# Main.net
KiCad netlist of a schematic drawn in Altium Designer
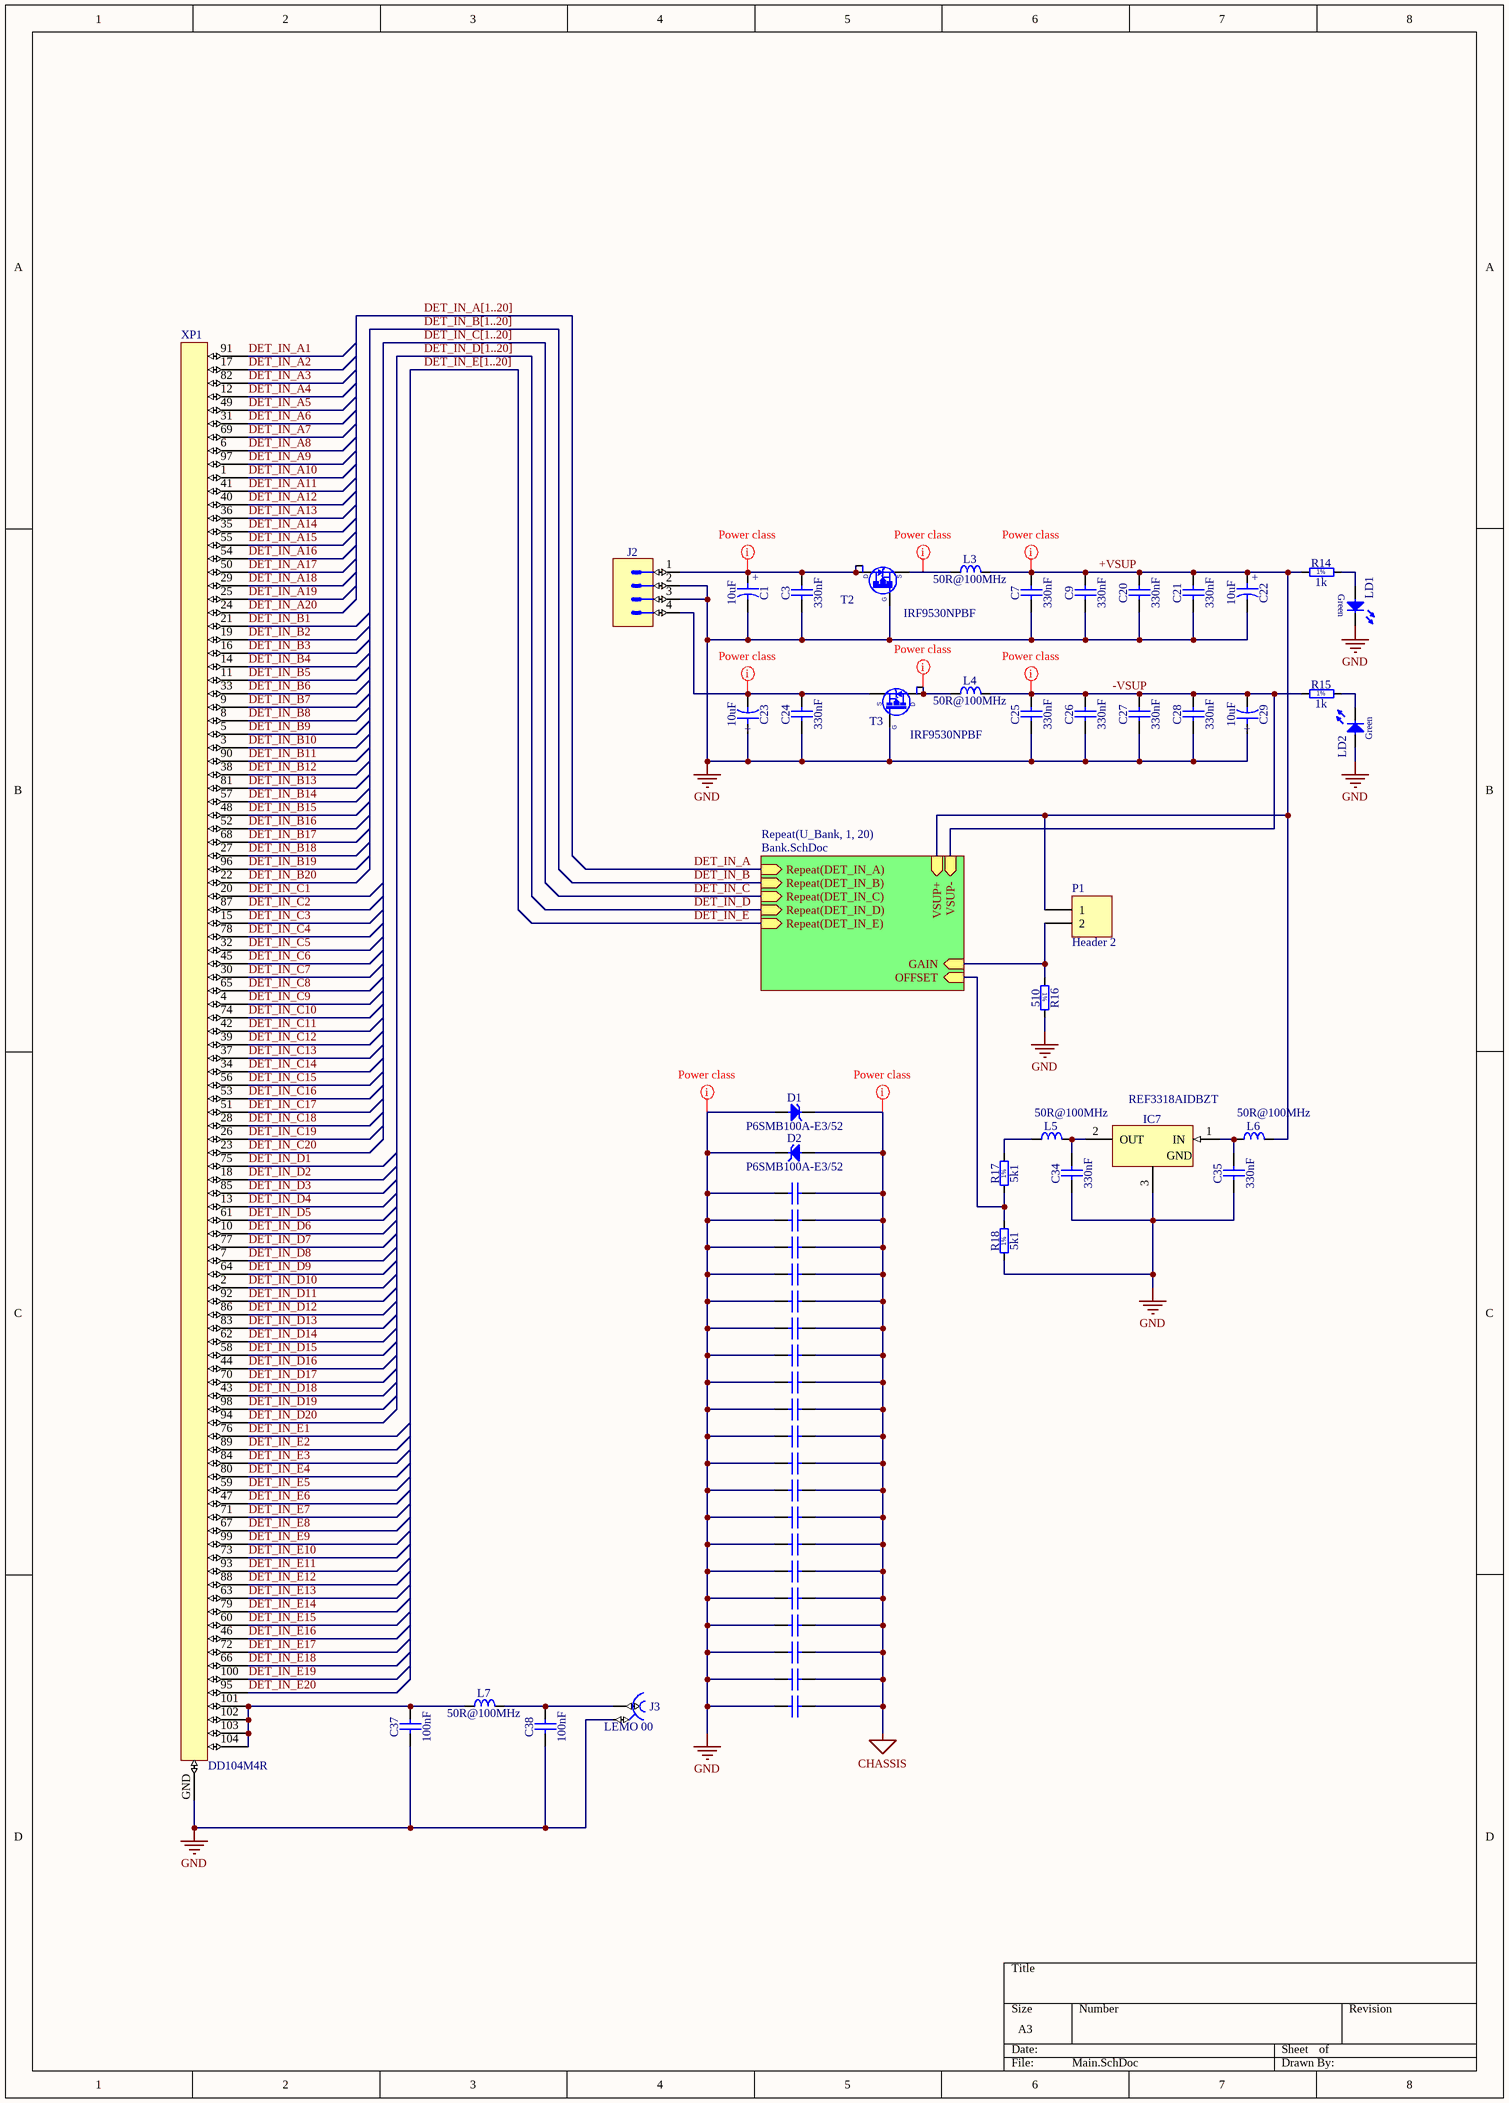
[diagram p0: Main.SchDoc]

(export (version "E")
  (design (tool "Eeschema 10.0.6"))
  (components
    (comp (ref "C1")
      (value "10uF")
      (footprint "CAPAE430X540N")
      (description "Polarised capacitor")
      (fields
        (field (name "PART NUMBER") "CAE430-540_10UF_16V_20%")
        (field (name "VOLTAGE") "16V")
        (field (name "AUTHOR") "CERN DEM JLC")
      )
      (libsource (lib "Capacitors") (part "Capacitor - polarized"))
    )
    (comp (ref "C3")
      (value "330nF")
      (footprint "CAPC2012X145N")
      (description "Non-polarised capacitor")
      (fields
        (field (name "PART NUMBER") "CC0805_330NF_50V_20%_X5R")
        (field (name "VOLTAGE") "50V")
        (field (name "AUTHOR") "CERN DEM MR")
      )
      (libsource (lib "Capacitors") (part "Capacitor - non polarized"))
    )
    (comp (ref "C7")
      (value "330nF")
      (footprint "CAPC2012X145N")
      (description "Non-polarised capacitor")
      (fields
        (field (name "PART NUMBER") "CC0805_330NF_50V_20%_X5R")
        (field (name "VOLTAGE") "50V")
        (field (name "AUTHOR") "CERN DEM MR")
      )
      (libsource (lib "Capacitors") (part "Capacitor - non polarized"))
    )
    (comp (ref "C9")
      (value "330nF")
      (footprint "CAPC2012X145N")
      (description "Non-polarised capacitor")
      (fields
        (field (name "PART NUMBER") "CC0805_330NF_50V_20%_X5R")
        (field (name "VOLTAGE") "50V")
        (field (name "AUTHOR") "CERN DEM MR")
      )
      (libsource (lib "Capacitors") (part "Capacitor - non polarized"))
    )
    (comp (ref "C20")
      (value "330nF")
      (footprint "CAPC2012X145N")
      (description "Non-polarised capacitor")
      (fields
        (field (name "PART NUMBER") "CC0805_330NF_50V_20%_X5R")
        (field (name "VOLTAGE") "50V")
        (field (name "AUTHOR") "CERN DEM MR")
      )
      (libsource (lib "Capacitors") (part "Capacitor - non polarized"))
    )
    (comp (ref "C21")
      (value "330nF")
      (footprint "CAPC2012X145N")
      (description "Non-polarised capacitor")
      (fields
        (field (name "PART NUMBER") "CC0805_330NF_50V_20%_X5R")
        (field (name "VOLTAGE") "50V")
        (field (name "AUTHOR") "CERN DEM MR")
      )
      (libsource (lib "Capacitors") (part "Capacitor - non polarized"))
    )
    (comp (ref "C22")
      (value "10uF")
      (footprint "CAPAE430X540N")
      (description "Polarised capacitor")
      (fields
        (field (name "PART NUMBER") "CAE430-540_10UF_16V_20%")
        (field (name "VOLTAGE") "16V")
        (field (name "AUTHOR") "CERN DEM JLC")
      )
      (libsource (lib "Capacitors") (part "Capacitor - polarized"))
    )
    (comp (ref "C23")
      (value "10uF")
      (footprint "CAPAE430X540N")
      (description "Polarised capacitor")
      (fields
        (field (name "PART NUMBER") "CAE430-540_10UF_16V_20%")
        (field (name "VOLTAGE") "16V")
        (field (name "AUTHOR") "CERN DEM JLC")
      )
      (libsource (lib "") (part "Capacitor - polarized_1"))
    )
    (comp (ref "C24")
      (value "330nF")
      (footprint "CAPC2012X145N")
      (description "Non-polarised capacitor")
      (fields
        (field (name "PART NUMBER") "CC0805_330NF_50V_20%_X5R")
        (field (name "VOLTAGE") "50V")
        (field (name "AUTHOR") "CERN DEM MR")
      )
      (libsource (lib "Capacitors") (part "Capacitor - non polarized"))
    )
    (comp (ref "C25")
      (value "330nF")
      (footprint "CAPC2012X145N")
      (description "Non-polarised capacitor")
      (fields
        (field (name "PART NUMBER") "CC0805_330NF_50V_20%_X5R")
        (field (name "VOLTAGE") "50V")
        (field (name "AUTHOR") "CERN DEM MR")
      )
      (libsource (lib "Capacitors") (part "Capacitor - non polarized"))
    )
    (comp (ref "C26")
      (value "330nF")
      (footprint "CAPC2012X145N")
      (description "Non-polarised capacitor")
      (fields
        (field (name "PART NUMBER") "CC0805_330NF_50V_20%_X5R")
        (field (name "VOLTAGE") "50V")
        (field (name "AUTHOR") "CERN DEM MR")
      )
      (libsource (lib "Capacitors") (part "Capacitor - non polarized"))
    )
    (comp (ref "C27")
      (value "330nF")
      (footprint "CAPC2012X145N")
      (description "Non-polarised capacitor")
      (fields
        (field (name "PART NUMBER") "CC0805_330NF_50V_20%_X5R")
        (field (name "VOLTAGE") "50V")
        (field (name "AUTHOR") "CERN DEM MR")
      )
      (libsource (lib "Capacitors") (part "Capacitor - non polarized"))
    )
    (comp (ref "C28")
      (value "330nF")
      (footprint "CAPC2012X145N")
      (description "Non-polarised capacitor")
      (fields
        (field (name "PART NUMBER") "CC0805_330NF_50V_20%_X5R")
        (field (name "VOLTAGE") "50V")
        (field (name "AUTHOR") "CERN DEM MR")
      )
      (libsource (lib "Capacitors") (part "Capacitor - non polarized"))
    )
    (comp (ref "C29")
      (value "10uF")
      (footprint "CAPAE430X540N")
      (description "Polarised capacitor")
      (fields
        (field (name "PART NUMBER") "CAE430-540_10UF_16V_20%")
        (field (name "VOLTAGE") "16V")
        (field (name "AUTHOR") "CERN DEM JLC")
      )
      (libsource (lib "") (part "Capacitor - polarized_1"))
    )
    (comp (ref "C31")
      (value "100nF")
      (footprint "CAPC3216X140N")
      (description "Non-polarised capacitor")
      (fields
        (field (name "PART NUMBER") "CC1206_100NF_200V_10%_X7R")
        (field (name "VOLTAGE") "200V")
        (field (name "AUTHOR") "CERN DEM JLC")
      )
      (libsource (lib "Capacitors") (part "Capacitor - non polarized"))
    )
    (comp (ref "C32")
      (value "100nF")
      (footprint "CAPC3216X140N")
      (description "Non-polarised capacitor")
      (fields
        (field (name "PART NUMBER") "CC1206_100NF_200V_10%_X7R")
        (field (name "VOLTAGE") "200V")
        (field (name "AUTHOR") "CERN DEM JLC")
      )
      (libsource (lib "Capacitors") (part "Capacitor - non polarized"))
    )
    (comp (ref "C33")
      (value "100nF")
      (footprint "CAPC3216X140N")
      (description "Non-polarised capacitor")
      (fields
        (field (name "PART NUMBER") "CC1206_100NF_200V_10%_X7R")
        (field (name "VOLTAGE") "200V")
        (field (name "AUTHOR") "CERN DEM JLC")
      )
      (libsource (lib "Capacitors") (part "Capacitor - non polarized"))
    )
    (comp (ref "C34")
      (value "330nF")
      (footprint "CAPC2012X145N")
      (description "Non-polarised capacitor")
      (fields
        (field (name "PART NUMBER") "CC0805_330NF_50V_20%_X5R")
        (field (name "VOLTAGE") "50V")
        (field (name "AUTHOR") "CERN DEM MR")
      )
      (libsource (lib "Capacitors") (part "Capacitor - non polarized"))
    )
    (comp (ref "C35")
      (value "330nF")
      (footprint "CAPC2012X145N")
      (description "Non-polarised capacitor")
      (fields
        (field (name "PART NUMBER") "CC0805_330NF_50V_20%_X5R")
        (field (name "VOLTAGE") "50V")
        (field (name "AUTHOR") "CERN DEM MR")
      )
      (libsource (lib "Capacitors") (part "Capacitor - non polarized"))
    )
    (comp (ref "C36")
      (value "100nF")
      (footprint "CAPC3216X140N")
      (description "Non-polarised capacitor")
      (fields
        (field (name "PART NUMBER") "CC1206_100NF_200V_10%_X7R")
        (field (name "VOLTAGE") "200V")
        (field (name "AUTHOR") "CERN DEM JLC")
      )
      (libsource (lib "Capacitors") (part "Capacitor - non polarized"))
    )
    (comp (ref "C37")
      (value "100nF")
      (footprint "CAPC3216X140N")
      (description "Non-polarised capacitor")
      (fields
        (field (name "PART NUMBER") "CC1206_100NF_200V_10%_X7R")
        (field (name "VOLTAGE") "200V")
        (field (name "AUTHOR") "CERN DEM JLC")
      )
      (libsource (lib "Capacitors") (part "Capacitor - non polarized"))
    )
    (comp (ref "C38")
      (value "100nF")
      (footprint "CAPC3216X140N")
      (description "Non-polarised capacitor")
      (fields
        (field (name "PART NUMBER") "CC1206_100NF_200V_10%_X7R")
        (field (name "VOLTAGE") "200V")
        (field (name "AUTHOR") "CERN DEM JLC")
      )
      (libsource (lib "Capacitors") (part "Capacitor - non polarized"))
    )
    (comp (ref "C39")
      (value "100nF")
      (footprint "CAPC3216X140N")
      (description "Non-polarised capacitor")
      (fields
        (field (name "PART NUMBER") "CC1206_100NF_200V_10%_X7R")
        (field (name "VOLTAGE") "200V")
        (field (name "AUTHOR") "CERN DEM JLC")
      )
      (libsource (lib "Capacitors") (part "Capacitor - non polarized"))
    )
    (comp (ref "C40")
      (value "100nF")
      (footprint "CAPC3216X140N")
      (description "Non-polarised capacitor")
      (fields
        (field (name "PART NUMBER") "CC1206_100NF_200V_10%_X7R")
        (field (name "VOLTAGE") "200V")
        (field (name "AUTHOR") "CERN DEM JLC")
      )
      (libsource (lib "Capacitors") (part "Capacitor - non polarized"))
    )
    (comp (ref "C41")
      (value "100nF")
      (footprint "CAPC3216X140N")
      (description "Non-polarised capacitor")
      (fields
        (field (name "PART NUMBER") "CC1206_100NF_200V_10%_X7R")
        (field (name "VOLTAGE") "200V")
        (field (name "AUTHOR") "CERN DEM JLC")
      )
      (libsource (lib "Capacitors") (part "Capacitor - non polarized"))
    )
    (comp (ref "C42")
      (value "100nF")
      (footprint "CAPC3216X140N")
      (description "Non-polarised capacitor")
      (fields
        (field (name "PART NUMBER") "CC1206_100NF_200V_10%_X7R")
        (field (name "VOLTAGE") "200V")
        (field (name "AUTHOR") "CERN DEM JLC")
      )
      (libsource (lib "Capacitors") (part "Capacitor - non polarized"))
    )
    (comp (ref "C43")
      (value "100nF")
      (footprint "CAPC3216X140N")
      (description "Non-polarised capacitor")
      (fields
        (field (name "PART NUMBER") "CC1206_100NF_200V_10%_X7R")
        (field (name "VOLTAGE") "200V")
        (field (name "AUTHOR") "CERN DEM JLC")
      )
      (libsource (lib "Capacitors") (part "Capacitor - non polarized"))
    )
    (comp (ref "C44")
      (value "100nF")
      (footprint "CAPC3216X140N")
      (description "Non-polarised capacitor")
      (fields
        (field (name "PART NUMBER") "CC1206_100NF_200V_10%_X7R")
        (field (name "VOLTAGE") "200V")
        (field (name "AUTHOR") "CERN DEM JLC")
      )
      (libsource (lib "Capacitors") (part "Capacitor - non polarized"))
    )
    (comp (ref "C45")
      (value "100nF")
      (footprint "CAPC3216X140N")
      (description "Non-polarised capacitor")
      (fields
        (field (name "PART NUMBER") "CC1206_100NF_200V_10%_X7R")
        (field (name "VOLTAGE") "200V")
        (field (name "AUTHOR") "CERN DEM JLC")
      )
      (libsource (lib "Capacitors") (part "Capacitor - non polarized"))
    )
    (comp (ref "C46")
      (value "100nF")
      (footprint "CAPC3216X140N")
      (description "Non-polarised capacitor")
      (fields
        (field (name "PART NUMBER") "CC1206_100NF_200V_10%_X7R")
        (field (name "VOLTAGE") "200V")
        (field (name "AUTHOR") "CERN DEM JLC")
      )
      (libsource (lib "Capacitors") (part "Capacitor - non polarized"))
    )
    (comp (ref "C47")
      (value "100nF")
      (footprint "CAPC3216X140N")
      (description "Non-polarised capacitor")
      (fields
        (field (name "PART NUMBER") "CC1206_100NF_200V_10%_X7R")
        (field (name "VOLTAGE") "200V")
        (field (name "AUTHOR") "CERN DEM JLC")
      )
      (libsource (lib "Capacitors") (part "Capacitor - non polarized"))
    )
    (comp (ref "C48")
      (value "100nF")
      (footprint "CAPC3216X140N")
      (description "Non-polarised capacitor")
      (fields
        (field (name "PART NUMBER") "CC1206_100NF_200V_10%_X7R")
        (field (name "VOLTAGE") "200V")
        (field (name "AUTHOR") "CERN DEM JLC")
      )
      (libsource (lib "Capacitors") (part "Capacitor - non polarized"))
    )
    (comp (ref "C49")
      (value "100nF")
      (footprint "CAPC3216X140N")
      (description "Non-polarised capacitor")
      (fields
        (field (name "PART NUMBER") "CC1206_100NF_200V_10%_X7R")
        (field (name "VOLTAGE") "200V")
        (field (name "AUTHOR") "CERN DEM JLC")
      )
      (libsource (lib "Capacitors") (part "Capacitor - non polarized"))
    )
    (comp (ref "C50")
      (value "100nF")
      (footprint "CAPC3216X140N")
      (description "Non-polarised capacitor")
      (fields
        (field (name "PART NUMBER") "CC1206_100NF_200V_10%_X7R")
        (field (name "VOLTAGE") "200V")
        (field (name "AUTHOR") "CERN DEM JLC")
      )
      (libsource (lib "Capacitors") (part "Capacitor - non polarized"))
    )
    (comp (ref "C51")
      (value "100nF")
      (footprint "CAPC3216X140N")
      (description "Non-polarised capacitor")
      (fields
        (field (name "PART NUMBER") "CC1206_100NF_200V_10%_X7R")
        (field (name "VOLTAGE") "200V")
        (field (name "AUTHOR") "CERN DEM JLC")
      )
      (libsource (lib "Capacitors") (part "Capacitor - non polarized"))
    )
    (comp (ref "C52")
      (value "100nF")
      (footprint "CAPC3216X140N")
      (description "Non-polarised capacitor")
      (fields
        (field (name "PART NUMBER") "CC1206_100NF_200V_10%_X7R")
        (field (name "VOLTAGE") "200V")
        (field (name "AUTHOR") "CERN DEM JLC")
      )
      (libsource (lib "Capacitors") (part "Capacitor - non polarized"))
    )
    (comp (ref "C53")
      (value "100nF")
      (footprint "CAPC3216X140N")
      (description "Non-polarised capacitor")
      (fields
        (field (name "PART NUMBER") "CC1206_100NF_200V_10%_X7R")
        (field (name "VOLTAGE") "200V")
        (field (name "AUTHOR") "CERN DEM JLC")
      )
      (libsource (lib "Capacitors") (part "Capacitor - non polarized"))
    )
    (comp (ref "C54")
      (value "100nF")
      (footprint "CAPC3216X140N")
      (description "Non-polarised capacitor")
      (fields
        (field (name "PART NUMBER") "CC1206_100NF_200V_10%_X7R")
        (field (name "VOLTAGE") "200V")
        (field (name "AUTHOR") "CERN DEM JLC")
      )
      (libsource (lib "Capacitors") (part "Capacitor - non polarized"))
    )
    (comp (ref "D1")
      (value "P6SMB100A-E3/52")
      (footprint "DIOM5436X244N")
      (description "Transient Voltage Suppressor Diode (Uni-Directional)")
      (fields
        (field (name "VOLTAGE") "100V")
        (field (name "POWER") "600W")
        (field (name "AUTHOR") "CERN DEM JLC")
      )
      (libsource (lib "ICs And Semiconductors") (part "Diode TVS Uni-Directional"))
    )
    (comp (ref "D2")
      (value "P6SMB100A-E3/52")
      (footprint "DIOM5436X244N")
      (description "Transient Voltage Suppressor Diode (Uni-Directional)")
      (fields
        (field (name "VOLTAGE") "100V")
        (field (name "POWER") "600W")
        (field (name "AUTHOR") "CERN DEM JLC")
      )
      (libsource (lib "ICs And Semiconductors") (part "Diode TVS Uni-Directional"))
    )
    (comp (ref "IC7")
      (value "REF3318AIDBZT")
      (footprint "SOT95P237X112-3N")
      (description "3-Terminal Regulator 1=IN 2=OUT 3=GND")
      (fields (field (name "MANUFACTURER") "TEXAS INSTRUMENTS") (field (name "AUTHOR") "CERN DEM JLC"))
      (libsource (lib "ICs And Semiconductors") (part "REG3 1IN-2OUT-3GND"))
    )
    (comp (ref "J2")
      (value "Header 4")
      (footprint "WURTH_691 313 410 004")
      (description "Connector 4 Male")
      (fields
        (field (name "PART NUMBER") "WURTH_691 313 410 004")
        (field (name "MANUFACTURER") "WURTH ELEKTRONIK")
        (field (name "AUTHOR") "CERN DEM MR")
      )
      (libsource (lib "Connectors") (part "Connector 4 Male"))
    )
    (comp (ref "J3")
      (value "LEMO 00")
      (footprint "LEMO_EPK.00.250.NTN")
      (fields
        (field (name "PART NUMBER") "LEMO_EPK.00.250.NTN")
        (field (name "MANUFACTURER") "LEMO")
        (field (name "MANUFACTURER PART NUMBER") "EPK.00.250.NTN")
        (field (name "AUTHOR") "CERN DEM JLC")
      )
      (libsource (lib "Connectors") (part "Coax_1Female_1Shield"))
    )
    (comp (ref "L3")
      (value "50R@100MHz")
      (footprint "IND_MURATA_BLM31PG")
      (description "Inductor")
      (fields
        (field (name "PART NUMBER") "IND1206_MURATA_BLM31PG500SN1")
        (field (name "POWER") "3.5A")
        (field (name "AUTHOR") "CERN DEM JLC")
      )
      (libsource (lib "Inductors & Transformers") (part "Inductor"))
    )
    (comp (ref "L4")
      (value "50R@100MHz")
      (footprint "IND_MURATA_BLM31PG")
      (description "Inductor")
      (fields
        (field (name "PART NUMBER") "IND1206_MURATA_BLM31PG500SN1")
        (field (name "POWER") "3.5A")
        (field (name "AUTHOR") "CERN DEM JLC")
      )
      (libsource (lib "Inductors & Transformers") (part "Inductor"))
    )
    (comp (ref "L5")
      (value "50R@100MHz")
      (footprint "IND_MURATA_BLM31PG")
      (description "Inductor")
      (fields
        (field (name "PART NUMBER") "IND1206_MURATA_BLM31PG500SN1")
        (field (name "POWER") "3.5A")
        (field (name "AUTHOR") "CERN DEM JLC")
      )
      (libsource (lib "Inductors & Transformers") (part "Inductor"))
    )
    (comp (ref "L6")
      (value "50R@100MHz")
      (footprint "IND_MURATA_BLM31PG")
      (description "Inductor")
      (fields
        (field (name "PART NUMBER") "IND1206_MURATA_BLM31PG500SN1")
        (field (name "POWER") "3.5A")
        (field (name "AUTHOR") "CERN DEM JLC")
      )
      (libsource (lib "Inductors & Transformers") (part "Inductor"))
    )
    (comp (ref "L7")
      (value "50R@100MHz")
      (footprint "IND_MURATA_BLM31PG")
      (description "Inductor")
      (fields
        (field (name "PART NUMBER") "IND1206_MURATA_BLM31PG500SN1")
        (field (name "POWER") "3.5A")
        (field (name "AUTHOR") "CERN DEM JLC")
      )
      (libsource (lib "Inductors & Transformers") (part "Inductor"))
    )
    (comp (ref "LD1")
      (value "Green")
      (footprint "LED_OSRAM_LGR971")
      (description "LED Green 1C 2A")
      (fields
        (field (name "PART NUMBER") "LED_OSRAM_LGR971")
        (field (name "MANUFACTURER") "OSRAM")
        (field (name "AUTHOR") "CERN DEM JLC")
      )
      (libsource (lib "ICs And Semiconductors") (part "LED Green 1C 2A"))
    )
    (comp (ref "LD2")
      (value "Green")
      (footprint "LED_OSRAM_LGR971")
      (description "LED Green 1C 2A")
      (fields
        (field (name "PART NUMBER") "LED_OSRAM_LGR971")
        (field (name "MANUFACTURER") "OSRAM")
        (field (name "AUTHOR") "CERN DEM JLC")
      )
      (libsource (lib "ICs And Semiconductors") (part "LED Green 1C 2A"))
    )
    (comp (ref "P1")
      (value "Header 2")
      (footprint "HDR1X2")
      (description "Header, 2-Pin")
      (fields (field (name "PUBLISHER") "Altium Limited"))
      (libsource (lib "Miscellaneous Connectors") (part "Header 2"))
    )
    (comp (ref "R14")
      (value "1k")
      (footprint "RESC2012X60N")
      (description "Resistor - 1%")
      (fields
        (field (name "PART NUMBER") "R0805_1K_1%_0.125W_100PPM")
        (field (name "POWER") "0.125W")
        (field (name "AUTHOR") "CERN DEM JLC")
      )
      (libsource (lib "Resistors") (part "Resistor - 1%"))
    )
    (comp (ref "R15")
      (value "1k")
      (footprint "RESC2012X60N")
      (description "Resistor - 1%")
      (fields
        (field (name "PART NUMBER") "R0805_1K_1%_0.125W_100PPM")
        (field (name "POWER") "0.125W")
        (field (name "AUTHOR") "CERN DEM JLC")
      )
      (libsource (lib "Resistors") (part "Resistor - 1%"))
    )
    (comp (ref "R16")
      (value "510")
      (footprint "RESC2012X60N")
      (description "Resistor - 1%")
      (fields
        (field (name "PART NUMBER") "R0805_510R_1%_0.125W_100PPM")
        (field (name "POWER") "0.125W")
        (field (name "AUTHOR") "CERN DEM JLC")
      )
      (libsource (lib "Resistors") (part "Resistor - 1%"))
    )
    (comp (ref "R17")
      (value "5k1")
      (footprint "RESC2012X60N")
      (description "Resistor - 1%")
      (fields
        (field (name "PART NUMBER") "R0805_5K1_1%_0.125W_100PPM")
        (field (name "POWER") "0.125W")
        (field (name "AUTHOR") "CERN DEM JLC")
      )
      (libsource (lib "Resistors") (part "Resistor - 1%"))
    )
    (comp (ref "R18")
      (value "5k1")
      (footprint "RESC2012X60N")
      (description "Resistor - 1%")
      (fields
        (field (name "PART NUMBER") "R0805_5K1_1%_0.125W_100PPM")
        (field (name "POWER") "0.125W")
        (field (name "AUTHOR") "CERN DEM JLC")
      )
      (libsource (lib "Resistors") (part "Resistor - 1%"))
    )
    (comp (ref "T2")
      (value "IRF9530NPBF")
      (footprint "TO-220-H")
      (description "P-CHANNEL MOSFET WITH ZENER DIODE")
      (fields
        (field (name "PART NUMBER") "IRF9530NPBF_h")
        (field (name "MANUFACTURER") "INTERNATIONAL RECTIFIER")
        (field (name "AUTHOR") "CERN DEM MR")
      )
      (libsource (lib "") (part "P-MOSFET-DZ 1G 2D 3S 4D_1"))
    )
    (comp (ref "T3")
      (value "IRF9530NPBF")
      (footprint "TO-220-H")
      (description "P-CHANNEL MOSFET WITH ZENER DIODE")
      (fields
        (field (name "PART NUMBER") "IRF9530NPBF_h")
        (field (name "MANUFACTURER") "INTERNATIONAL RECTIFIER")
        (field (name "AUTHOR") "CERN DEM MR")
      )
      (libsource (lib "ICs And Semiconductors") (part "P-MOSFET-DZ 1G 2D 3S 4D"))
    )
    (comp (ref "XP1") (value "DD104M4R") (footprint "DB104") (libsource (lib "Schlib") (part "DD104M4R")))
  )
  (nets
    (net (code "1") (name "/+VSUP") (class "Default")
      (node (ref "C20") (pin "2") (pinfunction "2_2") (pintype "passive"))
      (node (ref "C21") (pin "2") (pinfunction "2_2") (pintype "passive"))
      (node (ref "C22") (pin "1") (pinfunction "1_1") (pintype "passive"))
      (node (ref "C7") (pin "2") (pinfunction "2_2") (pintype "passive"))
      (node (ref "C9") (pin "2") (pinfunction "2_2") (pintype "passive"))
      (node (ref "L3") (pin "2") (pinfunction "2_2") (pintype "passive"))
      (node (ref "L6") (pin "2") (pinfunction "2_2") (pintype "passive"))
      (node (ref "P1") (pin "1") (pinfunction "1_1") (pintype "passive"))
      (node (ref "R14") (pin "1") (pinfunction "1_1") (pintype "passive"))
    )
    (net (code "2") (name "/-VSUP") (class "Default")
      (node (ref "C25") (pin "2") (pinfunction "2_2") (pintype "passive"))
      (node (ref "C26") (pin "2") (pinfunction "2_2") (pintype "passive"))
      (node (ref "C27") (pin "2") (pinfunction "2_2") (pintype "passive"))
      (node (ref "C28") (pin "2") (pinfunction "2_2") (pintype "passive"))
      (node (ref "C29") (pin "2") (pinfunction "2_2") (pintype "passive"))
      (node (ref "L4") (pin "2") (pinfunction "2_2") (pintype "passive"))
      (node (ref "R15") (pin "1") (pinfunction "1_1") (pintype "passive"))
    )
    (net (code "4") (name "/DET_IN_A1") (class "Default")
      (node (ref "XP1") (pin "91") (pintype "bidirectional"))
    )
    (net (code "5") (name "/DET_IN_A2") (class "Default")
      (node (ref "XP1") (pin "17") (pintype "bidirectional"))
    )
    (net (code "6") (name "/DET_IN_A3") (class "Default")
      (node (ref "XP1") (pin "82") (pintype "bidirectional"))
    )
    (net (code "7") (name "/DET_IN_A4") (class "Default")
      (node (ref "XP1") (pin "12") (pintype "bidirectional"))
    )
    (net (code "8") (name "/DET_IN_A5") (class "Default")
      (node (ref "XP1") (pin "49") (pintype "bidirectional"))
    )
    (net (code "9") (name "/DET_IN_A6") (class "Default")
      (node (ref "XP1") (pin "31") (pintype "bidirectional"))
    )
    (net (code "10") (name "/DET_IN_A7") (class "Default")
      (node (ref "XP1") (pin "69") (pintype "bidirectional"))
    )
    (net (code "11") (name "/DET_IN_A8") (class "Default")
      (node (ref "XP1") (pin "6") (pintype "bidirectional"))
    )
    (net (code "12") (name "/DET_IN_A9") (class "Default")
      (node (ref "XP1") (pin "97") (pintype "bidirectional"))
    )
    (net (code "13") (name "/DET_IN_A10") (class "Default")
      (node (ref "XP1") (pin "1") (pintype "bidirectional"))
    )
    (net (code "14") (name "/DET_IN_A11") (class "Default")
      (node (ref "XP1") (pin "41") (pintype "bidirectional"))
    )
    (net (code "15") (name "/DET_IN_A12") (class "Default")
      (node (ref "XP1") (pin "40") (pintype "bidirectional"))
    )
    (net (code "16") (name "/DET_IN_A13") (class "Default")
      (node (ref "XP1") (pin "36") (pintype "bidirectional"))
    )
    (net (code "17") (name "/DET_IN_A14") (class "Default")
      (node (ref "XP1") (pin "35") (pintype "bidirectional"))
    )
    (net (code "18") (name "/DET_IN_A15") (class "Default")
      (node (ref "XP1") (pin "55") (pintype "bidirectional"))
    )
    (net (code "19") (name "/DET_IN_A16") (class "Default")
      (node (ref "XP1") (pin "54") (pintype "bidirectional"))
    )
    (net (code "20") (name "/DET_IN_A17") (class "Default")
      (node (ref "XP1") (pin "50") (pintype "bidirectional"))
    )
    (net (code "21") (name "/DET_IN_A18") (class "Default")
      (node (ref "XP1") (pin "29") (pintype "bidirectional"))
    )
    (net (code "22") (name "/DET_IN_A19") (class "Default")
      (node (ref "XP1") (pin "25") (pintype "bidirectional"))
    )
    (net (code "23") (name "/DET_IN_A20") (class "Default")
      (node (ref "XP1") (pin "24") (pintype "bidirectional"))
    )
    (net (code "26") (name "/DET_IN_B1") (class "Default")
      (node (ref "XP1") (pin "21") (pintype "bidirectional"))
    )
    (net (code "27") (name "/DET_IN_B2") (class "Default")
      (node (ref "XP1") (pin "19") (pintype "bidirectional"))
    )
    (net (code "28") (name "/DET_IN_B3") (class "Default")
      (node (ref "XP1") (pin "16") (pintype "bidirectional"))
    )
    (net (code "29") (name "/DET_IN_B4") (class "Default")
      (node (ref "XP1") (pin "14") (pintype "bidirectional"))
    )
    (net (code "30") (name "/DET_IN_B5") (class "Default")
      (node (ref "XP1") (pin "11") (pintype "bidirectional"))
    )
    (net (code "31") (name "/DET_IN_B6") (class "Default")
      (node (ref "XP1") (pin "33") (pintype "bidirectional"))
    )
    (net (code "32") (name "/DET_IN_B7") (class "Default")
      (node (ref "XP1") (pin "9") (pintype "bidirectional"))
    )
    (net (code "33") (name "/DET_IN_B8") (class "Default")
      (node (ref "XP1") (pin "8") (pintype "bidirectional"))
    )
    (net (code "34") (name "/DET_IN_B9") (class "Default")
      (node (ref "XP1") (pin "5") (pintype "bidirectional"))
    )
    (net (code "35") (name "/DET_IN_B10") (class "Default")
      (node (ref "XP1") (pin "3") (pintype "bidirectional"))
    )
    (net (code "36") (name "/DET_IN_B11") (class "Default")
      (node (ref "XP1") (pin "90") (pintype "bidirectional"))
    )
    (net (code "37") (name "/DET_IN_B12") (class "Default")
      (node (ref "XP1") (pin "38") (pintype "bidirectional"))
    )
    (net (code "38") (name "/DET_IN_B13") (class "Default")
      (node (ref "XP1") (pin "81") (pintype "bidirectional"))
    )
    (net (code "39") (name "/DET_IN_B14") (class "Default")
      (node (ref "XP1") (pin "57") (pintype "bidirectional"))
    )
    (net (code "40") (name "/DET_IN_B15") (class "Default")
      (node (ref "XP1") (pin "48") (pintype "bidirectional"))
    )
    (net (code "41") (name "/DET_IN_B16") (class "Default")
      (node (ref "XP1") (pin "52") (pintype "bidirectional"))
    )
    (net (code "42") (name "/DET_IN_B17") (class "Default")
      (node (ref "XP1") (pin "68") (pintype "bidirectional"))
    )
    (net (code "43") (name "/DET_IN_B18") (class "Default")
      (node (ref "XP1") (pin "27") (pintype "bidirectional"))
    )
    (net (code "44") (name "/DET_IN_B19") (class "Default")
      (node (ref "XP1") (pin "96") (pintype "bidirectional"))
    )
    (net (code "45") (name "/DET_IN_B20") (class "Default")
      (node (ref "XP1") (pin "22") (pintype "bidirectional"))
    )
    (net (code "48") (name "/DET_IN_C1") (class "Default")
      (node (ref "XP1") (pin "20") (pintype "bidirectional"))
    )
    (net (code "49") (name "/DET_IN_C2") (class "Default")
      (node (ref "XP1") (pin "87") (pintype "bidirectional"))
    )
    (net (code "50") (name "/DET_IN_C3") (class "Default")
      (node (ref "XP1") (pin "15") (pintype "bidirectional"))
    )
    (net (code "51") (name "/DET_IN_C4") (class "Default")
      (node (ref "XP1") (pin "78") (pintype "bidirectional"))
    )
    (net (code "52") (name "/DET_IN_C5") (class "Default")
      (node (ref "XP1") (pin "32") (pintype "bidirectional"))
    )
    (net (code "53") (name "/DET_IN_C6") (class "Default")
      (node (ref "XP1") (pin "45") (pintype "bidirectional"))
    )
    (net (code "54") (name "/DET_IN_C7") (class "Default")
      (node (ref "XP1") (pin "30") (pintype "bidirectional"))
    )
    (net (code "55") (name "/DET_IN_C8") (class "Default")
      (node (ref "XP1") (pin "65") (pintype "bidirectional"))
    )
    (net (code "56") (name "/DET_IN_C9") (class "Default")
      (node (ref "XP1") (pin "4") (pintype "bidirectional"))
    )
    (net (code "57") (name "/DET_IN_C10") (class "Default")
      (node (ref "XP1") (pin "74") (pintype "bidirectional"))
    )
    (net (code "58") (name "/DET_IN_C11") (class "Default")
      (node (ref "XP1") (pin "42") (pintype "bidirectional"))
    )
    (net (code "59") (name "/DET_IN_C12") (class "Default")
      (node (ref "XP1") (pin "39") (pintype "bidirectional"))
    )
    (net (code "60") (name "/DET_IN_C13") (class "Default")
      (node (ref "XP1") (pin "37") (pintype "bidirectional"))
    )
    (net (code "61") (name "/DET_IN_C14") (class "Default")
      (node (ref "XP1") (pin "34") (pintype "bidirectional"))
    )
    (net (code "62") (name "/DET_IN_C15") (class "Default")
      (node (ref "XP1") (pin "56") (pintype "bidirectional"))
    )
    (net (code "63") (name "/DET_IN_C16") (class "Default")
      (node (ref "XP1") (pin "53") (pintype "bidirectional"))
    )
    (net (code "64") (name "/DET_IN_C17") (class "Default")
      (node (ref "XP1") (pin "51") (pintype "bidirectional"))
    )
    (net (code "65") (name "/DET_IN_C18") (class "Default")
      (node (ref "XP1") (pin "28") (pintype "bidirectional"))
    )
    (net (code "66") (name "/DET_IN_C19") (class "Default")
      (node (ref "XP1") (pin "26") (pintype "bidirectional"))
    )
    (net (code "67") (name "/DET_IN_C20") (class "Default")
      (node (ref "XP1") (pin "23") (pintype "bidirectional"))
    )
    (net (code "70") (name "/DET_IN_D1") (class "Default")
      (node (ref "XP1") (pin "75") (pintype "bidirectional"))
    )
    (net (code "71") (name "/DET_IN_D2") (class "Default")
      (node (ref "XP1") (pin "18") (pintype "bidirectional"))
    )
    (net (code "72") (name "/DET_IN_D3") (class "Default")
      (node (ref "XP1") (pin "85") (pintype "bidirectional"))
    )
    (net (code "73") (name "/DET_IN_D4") (class "Default")
      (node (ref "XP1") (pin "13") (pintype "bidirectional"))
    )
    (net (code "74") (name "/DET_IN_D5") (class "Default")
      (node (ref "XP1") (pin "61") (pintype "bidirectional"))
    )
    (net (code "75") (name "/DET_IN_D6") (class "Default")
      (node (ref "XP1") (pin "10") (pintype "bidirectional"))
    )
    (net (code "76") (name "/DET_IN_D7") (class "Default")
      (node (ref "XP1") (pin "77") (pintype "bidirectional"))
    )
    (net (code "77") (name "/DET_IN_D8") (class "Default")
      (node (ref "XP1") (pin "7") (pintype "bidirectional"))
    )
    (net (code "78") (name "/DET_IN_D9") (class "Default")
      (node (ref "XP1") (pin "64") (pintype "bidirectional"))
    )
    (net (code "79") (name "/DET_IN_D10") (class "Default")
      (node (ref "XP1") (pin "2") (pintype "bidirectional"))
    )
    (net (code "80") (name "/DET_IN_D11") (class "Default")
      (node (ref "XP1") (pin "92") (pintype "bidirectional"))
    )
    (net (code "81") (name "/DET_IN_D12") (class "Default")
      (node (ref "XP1") (pin "86") (pintype "bidirectional"))
    )
    (net (code "82") (name "/DET_IN_D13") (class "Default")
      (node (ref "XP1") (pin "83") (pintype "bidirectional"))
    )
    (net (code "83") (name "/DET_IN_D14") (class "Default")
      (node (ref "XP1") (pin "62") (pintype "bidirectional"))
    )
    (net (code "84") (name "/DET_IN_D15") (class "Default")
      (node (ref "XP1") (pin "58") (pintype "bidirectional"))
    )
    (net (code "85") (name "/DET_IN_D16") (class "Default")
      (node (ref "XP1") (pin "44") (pintype "bidirectional"))
    )
    (net (code "86") (name "/DET_IN_D17") (class "Default")
      (node (ref "XP1") (pin "70") (pintype "bidirectional"))
    )
    (net (code "87") (name "/DET_IN_D18") (class "Default")
      (node (ref "XP1") (pin "43") (pintype "bidirectional"))
    )
    (net (code "88") (name "/DET_IN_D19") (class "Default")
      (node (ref "XP1") (pin "98") (pintype "bidirectional"))
    )
    (net (code "89") (name "/DET_IN_D20") (class "Default")
      (node (ref "XP1") (pin "94") (pintype "bidirectional"))
    )
    (net (code "92") (name "/DET_IN_E1") (class "Default")
      (node (ref "XP1") (pin "76") (pintype "bidirectional"))
    )
    (net (code "93") (name "/DET_IN_E2") (class "Default")
      (node (ref "XP1") (pin "89") (pintype "bidirectional"))
    )
    (net (code "94") (name "/DET_IN_E3") (class "Default")
      (node (ref "XP1") (pin "84") (pintype "bidirectional"))
    )
    (net (code "95") (name "/DET_IN_E4") (class "Default")
      (node (ref "XP1") (pin "80") (pintype "bidirectional"))
    )
    (net (code "96") (name "/DET_IN_E5") (class "Default")
      (node (ref "XP1") (pin "59") (pintype "bidirectional"))
    )
    (net (code "97") (name "/DET_IN_E6") (class "Default")
      (node (ref "XP1") (pin "47") (pintype "bidirectional"))
    )
    (net (code "98") (name "/DET_IN_E7") (class "Default")
      (node (ref "XP1") (pin "71") (pintype "bidirectional"))
    )
    (net (code "99") (name "/DET_IN_E8") (class "Default")
      (node (ref "XP1") (pin "67") (pintype "bidirectional"))
    )
    (net (code "100") (name "/DET_IN_E9") (class "Default")
      (node (ref "XP1") (pin "99") (pintype "bidirectional"))
    )
    (net (code "101") (name "/DET_IN_E10") (class "Default")
      (node (ref "XP1") (pin "73") (pintype "bidirectional"))
    )
    (net (code "102") (name "/DET_IN_E11") (class "Default")
      (node (ref "XP1") (pin "93") (pintype "bidirectional"))
    )
    (net (code "103") (name "/DET_IN_E12") (class "Default")
      (node (ref "XP1") (pin "88") (pintype "bidirectional"))
    )
    (net (code "104") (name "/DET_IN_E13") (class "Default")
      (node (ref "XP1") (pin "63") (pintype "bidirectional"))
    )
    (net (code "105") (name "/DET_IN_E14") (class "Default")
      (node (ref "XP1") (pin "79") (pintype "bidirectional"))
    )
    (net (code "106") (name "/DET_IN_E15") (class "Default")
      (node (ref "XP1") (pin "60") (pintype "bidirectional"))
    )
    (net (code "107") (name "/DET_IN_E16") (class "Default")
      (node (ref "XP1") (pin "46") (pintype "bidirectional"))
    )
    (net (code "108") (name "/DET_IN_E17") (class "Default")
      (node (ref "XP1") (pin "72") (pintype "bidirectional"))
    )
    (net (code "109") (name "/DET_IN_E18") (class "Default")
      (node (ref "XP1") (pin "66") (pintype "bidirectional"))
    )
    (net (code "110") (name "/DET_IN_E19") (class "Default")
      (node (ref "XP1") (pin "100") (pintype "bidirectional"))
    )
    (net (code "111") (name "/DET_IN_E20") (class "Default")
      (node (ref "XP1") (pin "95") (pintype "bidirectional"))
    )
    (net (code "113") (name "/GAIN") (class "Default")
      (node (ref "P1") (pin "2") (pinfunction "2_2") (pintype "passive"))
      (node (ref "R16") (pin "1") (pinfunction "1_1") (pintype "passive"))
    )
    (net (code "114") (name "/OFFSET") (class "Default")
      (node (ref "R17") (pin "1") (pinfunction "1_1") (pintype "passive"))
      (node (ref "R18") (pin "2") (pinfunction "2_2") (pintype "passive"))
    )
    (net (code "115") (name "CHASSIS") (class "Default")
      (node (ref "C31") (pin "2") (pinfunction "2_2") (pintype "passive"))
      (node (ref "C32") (pin "2") (pinfunction "2_2") (pintype "passive"))
      (node (ref "C33") (pin "2") (pinfunction "2_2") (pintype "passive"))
      (node (ref "C36") (pin "2") (pinfunction "2_2") (pintype "passive"))
      (node (ref "C39") (pin "2") (pinfunction "2_2") (pintype "passive"))
      (node (ref "C40") (pin "2") (pinfunction "2_2") (pintype "passive"))
      (node (ref "C41") (pin "2") (pinfunction "2_2") (pintype "passive"))
      (node (ref "C42") (pin "2") (pinfunction "2_2") (pintype "passive"))
      (node (ref "C43") (pin "2") (pinfunction "2_2") (pintype "passive"))
      (node (ref "C44") (pin "2") (pinfunction "2_2") (pintype "passive"))
      (node (ref "C45") (pin "2") (pinfunction "2_2") (pintype "passive"))
      (node (ref "C46") (pin "2") (pinfunction "2_2") (pintype "passive"))
      (node (ref "C47") (pin "2") (pinfunction "2_2") (pintype "passive"))
      (node (ref "C48") (pin "2") (pinfunction "2_2") (pintype "passive"))
      (node (ref "C49") (pin "2") (pinfunction "2_2") (pintype "passive"))
      (node (ref "C50") (pin "2") (pinfunction "2_2") (pintype "passive"))
      (node (ref "C51") (pin "2") (pinfunction "2_2") (pintype "passive"))
      (node (ref "C52") (pin "2") (pinfunction "2_2") (pintype "passive"))
      (node (ref "C53") (pin "2") (pinfunction "2_2") (pintype "passive"))
      (node (ref "C54") (pin "2") (pinfunction "2_2") (pintype "passive"))
      (node (ref "D1") (pin "1") (pinfunction "C_1") (pintype "passive"))
      (node (ref "D2") (pin "2") (pinfunction "A_2") (pintype "passive"))
    )
    (net (code "116") (name "GND") (class "Default")
      (node (ref "C1") (pin "2") (pinfunction "2_2") (pintype "passive"))
      (node (ref "C20") (pin "1") (pinfunction "1_1") (pintype "passive"))
      (node (ref "C21") (pin "1") (pinfunction "1_1") (pintype "passive"))
      (node (ref "C22") (pin "2") (pinfunction "2_2") (pintype "passive"))
      (node (ref "C23") (pin "1") (pinfunction "1_1") (pintype "passive"))
      (node (ref "C24") (pin "1") (pinfunction "1_1") (pintype "passive"))
      (node (ref "C25") (pin "1") (pinfunction "1_1") (pintype "passive"))
      (node (ref "C26") (pin "1") (pinfunction "1_1") (pintype "passive"))
      (node (ref "C27") (pin "1") (pinfunction "1_1") (pintype "passive"))
      (node (ref "C28") (pin "1") (pinfunction "1_1") (pintype "passive"))
      (node (ref "C29") (pin "1") (pinfunction "1_1") (pintype "passive"))
      (node (ref "C3") (pin "1") (pinfunction "1_1") (pintype "passive"))
      (node (ref "C31") (pin "1") (pinfunction "1_1") (pintype "passive"))
      (node (ref "C32") (pin "1") (pinfunction "1_1") (pintype "passive"))
      (node (ref "C33") (pin "1") (pinfunction "1_1") (pintype "passive"))
      (node (ref "C34") (pin "1") (pinfunction "1_1") (pintype "passive"))
      (node (ref "C35") (pin "1") (pinfunction "1_1") (pintype "passive"))
      (node (ref "C36") (pin "1") (pinfunction "1_1") (pintype "passive"))
      (node (ref "C37") (pin "1") (pinfunction "1_1") (pintype "passive"))
      (node (ref "C38") (pin "1") (pinfunction "1_1") (pintype "passive"))
      (node (ref "C39") (pin "1") (pinfunction "1_1") (pintype "passive"))
      (node (ref "C40") (pin "1") (pinfunction "1_1") (pintype "passive"))
      (node (ref "C41") (pin "1") (pinfunction "1_1") (pintype "passive"))
      (node (ref "C42") (pin "1") (pinfunction "1_1") (pintype "passive"))
      (node (ref "C43") (pin "1") (pinfunction "1_1") (pintype "passive"))
      (node (ref "C44") (pin "1") (pinfunction "1_1") (pintype "passive"))
      (node (ref "C45") (pin "1") (pinfunction "1_1") (pintype "passive"))
      (node (ref "C46") (pin "1") (pinfunction "1_1") (pintype "passive"))
      (node (ref "C47") (pin "1") (pinfunction "1_1") (pintype "passive"))
      (node (ref "C48") (pin "1") (pinfunction "1_1") (pintype "passive"))
      (node (ref "C49") (pin "1") (pinfunction "1_1") (pintype "passive"))
      (node (ref "C50") (pin "1") (pinfunction "1_1") (pintype "passive"))
      (node (ref "C51") (pin "1") (pinfunction "1_1") (pintype "passive"))
      (node (ref "C52") (pin "1") (pinfunction "1_1") (pintype "passive"))
      (node (ref "C53") (pin "1") (pinfunction "1_1") (pintype "passive"))
      (node (ref "C54") (pin "1") (pinfunction "1_1") (pintype "passive"))
      (node (ref "C7") (pin "1") (pinfunction "1_1") (pintype "passive"))
      (node (ref "C9") (pin "1") (pinfunction "1_1") (pintype "passive"))
      (node (ref "D1") (pin "2") (pinfunction "A_2") (pintype "passive"))
      (node (ref "D2") (pin "1") (pinfunction "C_1") (pintype "passive"))
      (node (ref "IC7") (pin "3") (pinfunction "GND_3") (pintype "power_in"))
      (node (ref "J2") (pin "2") (pinfunction "2_2") (pintype "bidirectional"))
      (node (ref "J2") (pin "3") (pinfunction "3_3") (pintype "bidirectional"))
      (node (ref "J3") (pin "2") (pinfunction "2_2") (pintype "bidirectional"))
      (node (ref "LD1") (pin "1") (pinfunction "C_1") (pintype "passive"))
      (node (ref "LD2") (pin "2") (pinfunction "A_2") (pintype "passive"))
      (node (ref "R16") (pin "2") (pinfunction "2_2") (pintype "passive"))
      (node (ref "R18") (pin "1") (pinfunction "1_1") (pintype "passive"))
      (node (ref "T2") (pin "1") (pinfunction "G_1") (pintype "passive"))
      (node (ref "T3") (pin "1") (pinfunction "G_1") (pintype "passive"))
      (node (ref "XP1") (pin "GND") (pintype "bidirectional"))
    )
    (net (code "117") (name "Net-(C1-Pad1)") (class "Default")
      (node (ref "C1") (pin "1") (pinfunction "1_1") (pintype "passive"))
      (node (ref "C3") (pin "2") (pinfunction "2_2") (pintype "passive"))
      (node (ref "J2") (pin "1") (pinfunction "1_1") (pintype "bidirectional"))
      (node (ref "T2") (pin "2") (pinfunction "D_2") (pintype "passive"))
      (node (ref "T2") (pin "4") (pinfunction "D_4") (pintype "passive"))
    )
    (net (code "118") (name "Net-(C37-Pad2)") (class "Default")
      (node (ref "C37") (pin "2") (pinfunction "2_2") (pintype "passive"))
      (node (ref "L7") (pin "1") (pinfunction "1_1") (pintype "passive"))
      (node (ref "XP1") (pin "101") (pintype "bidirectional"))
      (node (ref "XP1") (pin "102") (pintype "bidirectional"))
      (node (ref "XP1") (pin "103") (pintype "bidirectional"))
      (node (ref "XP1") (pin "104") (pintype "bidirectional"))
    )
    (net (code "119") (name "Net-(C38-Pad2)") (class "Default")
      (node (ref "C38") (pin "2") (pinfunction "2_2") (pintype "passive"))
      (node (ref "J3") (pin "1") (pinfunction "1_1") (pintype "bidirectional"))
      (node (ref "L7") (pin "2") (pinfunction "2_2") (pintype "passive"))
    )
    (net (code "120") (name "Net-(IC7-IN)") (class "Default")
      (node (ref "C35") (pin "2") (pinfunction "2_2") (pintype "passive"))
      (node (ref "IC7") (pin "1") (pinfunction "IN_1") (pintype "input"))
      (node (ref "L6") (pin "1") (pinfunction "1_1") (pintype "passive"))
    )
    (net (code "121") (name "Net-(IC7-OUT)") (class "Default")
      (node (ref "C34") (pin "2") (pinfunction "2_2") (pintype "passive"))
      (node (ref "IC7") (pin "2") (pinfunction "OUT_2") (pintype "power_in"))
      (node (ref "L5") (pin "2") (pinfunction "2_2") (pintype "passive"))
    )
    (net (code "122") (name "Net-(L4-Pad1)") (class "Default")
      (node (ref "L4") (pin "1") (pinfunction "1_1") (pintype "passive"))
      (node (ref "T3") (pin "2") (pinfunction "D_2") (pintype "passive"))
      (node (ref "T3") (pin "4") (pinfunction "D_4") (pintype "passive"))
    )
    (net (code "123") (name "Net-(L5-Pad1)") (class "Default")
      (node (ref "L5") (pin "1") (pinfunction "1_1") (pintype "passive"))
      (node (ref "R17") (pin "2") (pinfunction "2_2") (pintype "passive"))
    )
    (net (code "124") (name "Net-(LD1-A)") (class "Default")
      (node (ref "LD1") (pin "2") (pinfunction "A_2") (pintype "passive"))
      (node (ref "R14") (pin "2") (pinfunction "2_2") (pintype "passive"))
    )
    (net (code "125") (name "Net-(LD2-C)") (class "Default")
      (node (ref "LD2") (pin "1") (pinfunction "C_1") (pintype "passive"))
      (node (ref "R15") (pin "2") (pinfunction "2_2") (pintype "passive"))
    )
    (net (code "126") (name "Net-(T2-S)") (class "Default")
      (node (ref "L3") (pin "1") (pinfunction "1_1") (pintype "passive"))
      (node (ref "T2") (pin "3") (pinfunction "S_3") (pintype "passive"))
    )
    (net (code "127") (name "Net-(T3-S)") (class "Default")
      (node (ref "C23") (pin "2") (pinfunction "2_2") (pintype "passive"))
      (node (ref "C24") (pin "2") (pinfunction "2_2") (pintype "passive"))
      (node (ref "J2") (pin "4") (pinfunction "4_4") (pintype "bidirectional"))
      (node (ref "T3") (pin "3") (pinfunction "S_3") (pintype "passive"))
    )
  )
)
